# V01.net
KiCad netlist of a schematic drawn in EAGLE
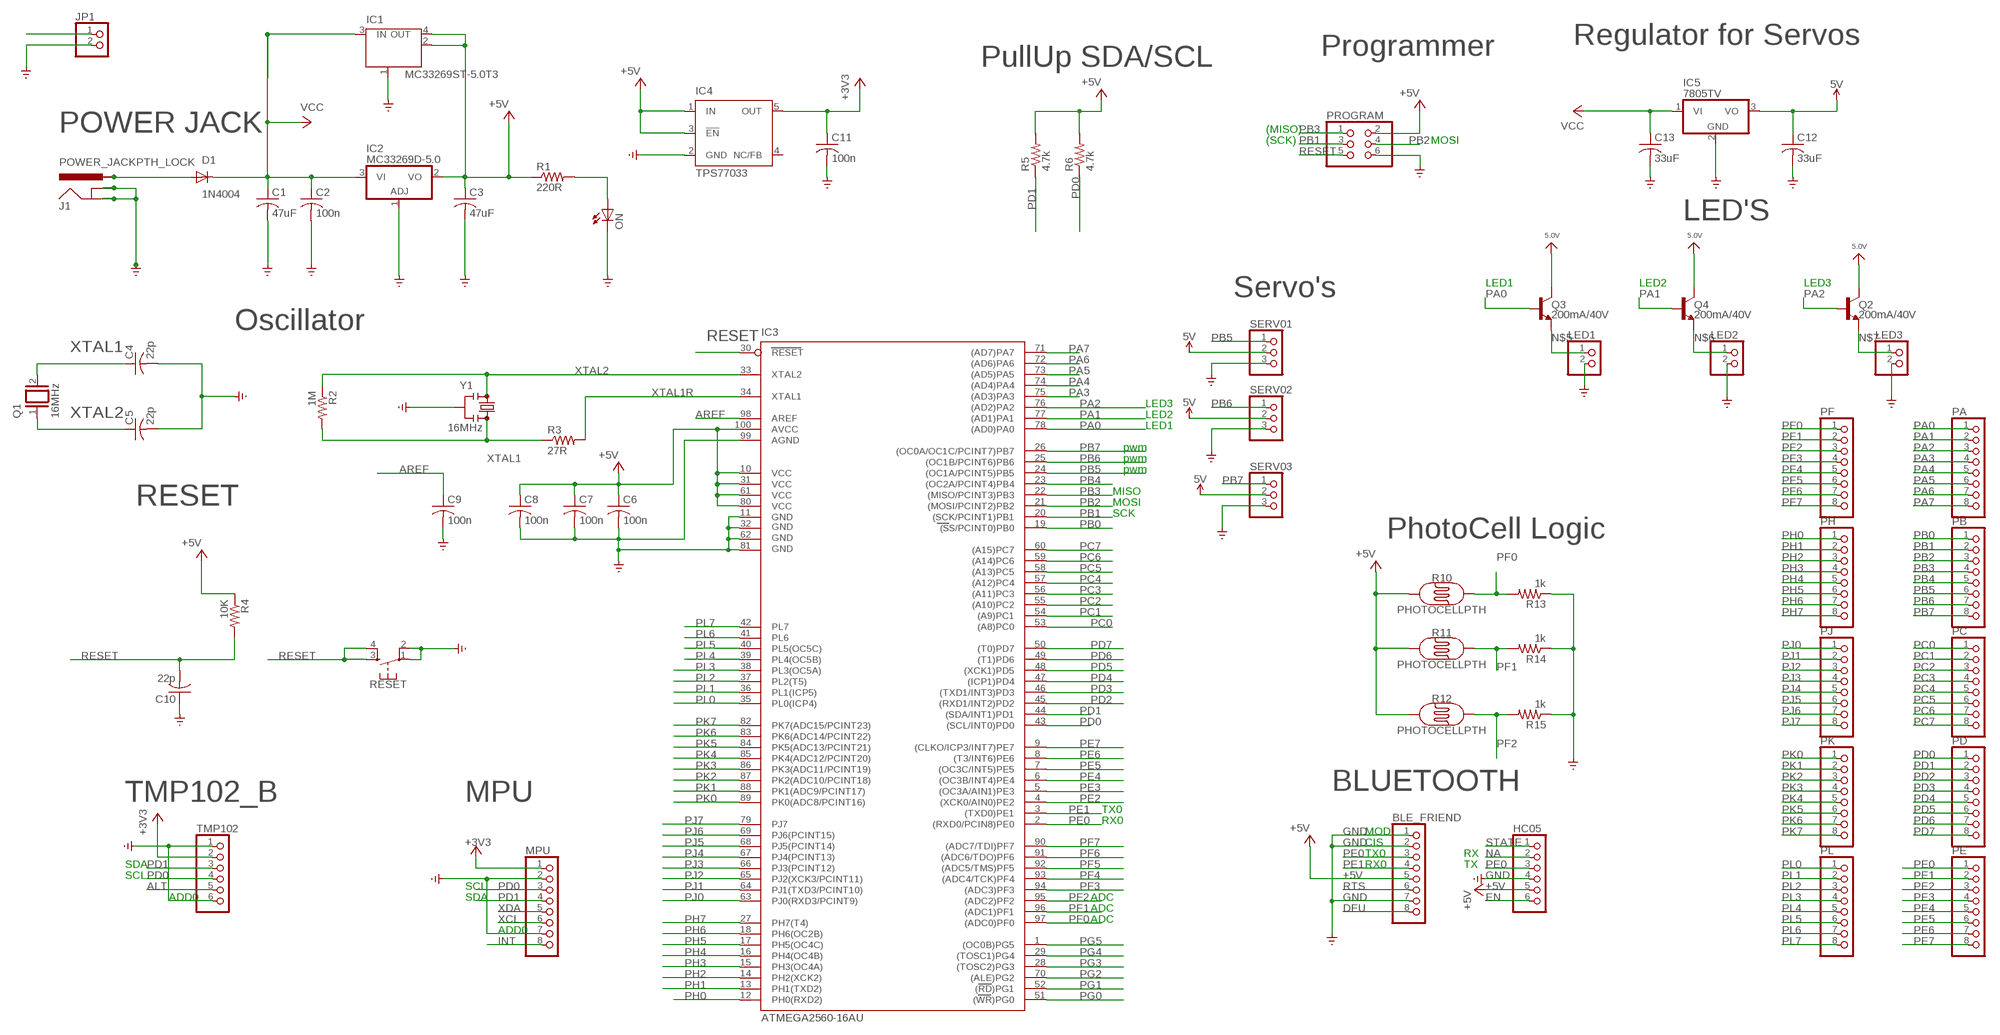
[diagram p0: schematic, sheet 1, part 1 of 2]
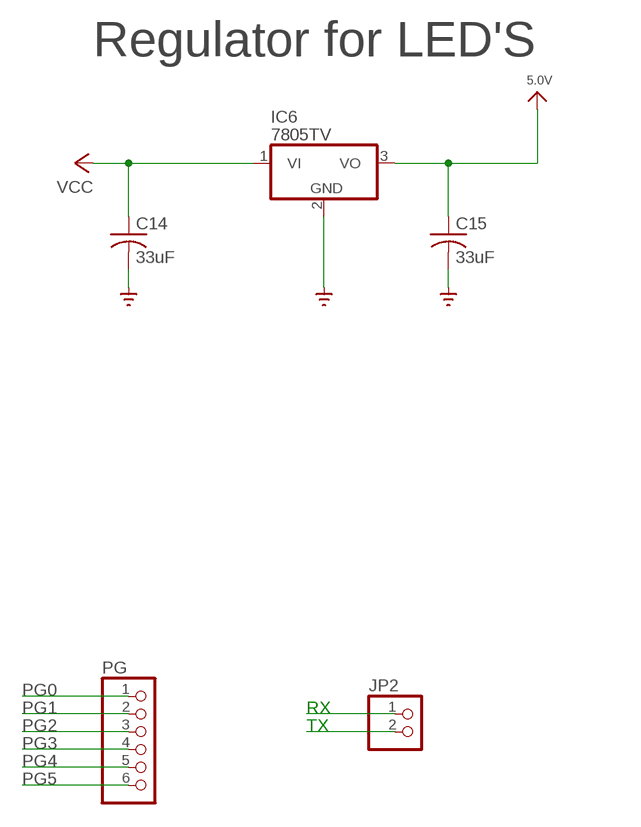
[diagram p1: schematic, sheet 1, part 2 of 2]

(export (version "E")
  (design (tool "Eeschema 10.0.6"))
  (components
    (comp (ref "BLE_FRIEND")
      (value "PINHD-1X8")
      (footprint "eagle-import:1X08")
      (libsource (lib "eagle-import") (part "PINHD-1X8"))
    )
    (comp (ref "C1")
      (value "47uF")
      (footprint "eagle-import:C025-024X044")
      (libsource (lib "eagle-import") (part "C-US025-024X044"))
    )
    (comp (ref "C2")
      (value "100n")
      (footprint "eagle-import:C025-024X044")
      (libsource (lib "eagle-import") (part "C-US025-024X044"))
    )
    (comp (ref "C3")
      (value "47uF")
      (footprint "eagle-import:C025-024X044")
      (libsource (lib "eagle-import") (part "C-US025-024X044"))
    )
    (comp (ref "C4")
      (value "22p")
      (footprint "eagle-import:C025-024X044")
      (libsource (lib "eagle-import") (part "C-US025-024X044"))
    )
    (comp (ref "C5")
      (value "22p")
      (footprint "eagle-import:C025-024X044")
      (libsource (lib "eagle-import") (part "C-US025-024X044"))
    )
    (comp (ref "C6")
      (value "100n")
      (footprint "eagle-import:C025-024X044")
      (libsource (lib "eagle-import") (part "C-US025-024X044"))
    )
    (comp (ref "C7")
      (value "100n")
      (footprint "eagle-import:C025-024X044")
      (libsource (lib "eagle-import") (part "C-US025-024X044"))
    )
    (comp (ref "C8")
      (value "100n")
      (footprint "eagle-import:C025-024X044")
      (libsource (lib "eagle-import") (part "C-US025-024X044"))
    )
    (comp (ref "C9")
      (value "100n")
      (footprint "eagle-import:C025-024X044")
      (libsource (lib "eagle-import") (part "C-US025-024X044"))
    )
    (comp (ref "C10")
      (value "22p")
      (footprint "eagle-import:C025-024X044")
      (libsource (lib "eagle-import") (part "C-US025-024X044"))
    )
    (comp (ref "C11")
      (value "100n")
      (footprint "eagle-import:C025-024X044")
      (libsource (lib "eagle-import") (part "C-US025-024X044"))
    )
    (comp (ref "C12")
      (value "33uF")
      (footprint "eagle-import:C025-024X044")
      (libsource (lib "eagle-import") (part "C-US025-024X044"))
    )
    (comp (ref "C13")
      (value "33uF")
      (footprint "eagle-import:C025-024X044")
      (libsource (lib "eagle-import") (part "C-US025-024X044"))
    )
    (comp (ref "C14")
      (value "33uF")
      (footprint "eagle-import:C025-024X044")
      (libsource (lib "eagle-import") (part "C-US025-024X044"))
    )
    (comp (ref "C15")
      (value "33uF")
      (footprint "eagle-import:C025-024X044")
      (libsource (lib "eagle-import") (part "C-US025-024X044"))
    )
    (comp (ref "D1")
      (value "1N4004")
      (footprint "eagle-import:DO41-10")
      (libsource (lib "eagle-import") (part "1N4004"))
    )
    (comp (ref "HC05")
      (value "PINHD-1X6")
      (footprint "eagle-import:1X06")
      (libsource (lib "eagle-import") (part "pinhead_325_PINHD-1X6"))
    )
    (comp (ref "IC1")
      (value "MC33269ST-5.0T3")
      (footprint "eagle-import:SOT223")
      (libsource (lib "eagle-import") (part "MC33269ST-3.3T3"))
    )
    (comp (ref "IC2")
      (value "MC33269D-5.0")
      (footprint "eagle-import:DPACK")
      (libsource (lib "eagle-import") (part "MC33269?D-5.0"))
    )
    (comp (ref "IC3")
      (value "ATMEGA2560-16AU")
      (footprint "eagle-import:TQFP100")
      (libsource (lib "eagle-import") (part "ATMEGAAU2560-16"))
    )
    (comp (ref "IC4")
      (value "TPS77033")
      (footprint "eagle-import:SOT23-DBV")
      (fields (field (name "MF") "TEXAS INSTRUMENTS") (field (name "MPN") "TPS77033DBVT"))
      (libsource (lib "eagle-import") (part "TPS77033"))
    )
    (comp (ref "IC5")
      (value "7805TV")
      (footprint "eagle-import:TO220V")
      (libsource (lib "eagle-import") (part "78TV05"))
    )
    (comp (ref "IC6")
      (value "7805TV")
      (footprint "eagle-import:TO220V")
      (libsource (lib "eagle-import") (part "78TV05"))
    )
    (comp (ref "J1")
      (value "POWER_JACKPTH_LOCK")
      (footprint "eagle-import:POWER_JACK_PTH_LOCK")
      (libsource (lib "eagle-import") (part "POWER_JACKPTH_LOCK"))
    )
    (comp (ref "JP1")
      (value "PINHD-1X2")
      (footprint "eagle-import:1X02")
      (libsource (lib "eagle-import") (part "PINHD-1X2"))
    )
    (comp (ref "JP2")
      (value "PINHD-1X2")
      (footprint "eagle-import:1X02")
      (libsource (lib "eagle-import") (part "pinhead_325_PINHD-1X2"))
    )
    (comp (ref "LED1")
      (value "PINHD-1X2")
      (footprint "eagle-import:1X02")
      (libsource (lib "eagle-import") (part "PINHD-1X2"))
    )
    (comp (ref "LED2")
      (value "PINHD-1X2")
      (footprint "eagle-import:1X02")
      (libsource (lib "eagle-import") (part "PINHD-1X2"))
    )
    (comp (ref "LED3")
      (value "PINHD-1X2")
      (footprint "eagle-import:1X02")
      (libsource (lib "eagle-import") (part "PINHD-1X2"))
    )
    (comp (ref "MPU")
      (value "PINHD-1X8")
      (footprint "eagle-import:1X08")
      (libsource (lib "eagle-import") (part "PINHD-1X8"))
    )
    (comp (ref "ON")
      (value "LED3MM")
      (footprint "eagle-import:LED3MM")
      (libsource (lib "eagle-import") (part "LED3MM"))
    )
    (comp (ref "PA")
      (value "PINHD-1X8")
      (footprint "eagle-import:1X08")
      (libsource (lib "eagle-import") (part "PINHD-1X8"))
    )
    (comp (ref "PB")
      (value "PINHD-1X8")
      (footprint "eagle-import:1X08")
      (libsource (lib "eagle-import") (part "PINHD-1X8"))
    )
    (comp (ref "PC")
      (value "PINHD-1X8")
      (footprint "eagle-import:1X08")
      (libsource (lib "eagle-import") (part "PINHD-1X8"))
    )
    (comp (ref "PD")
      (value "PINHD-1X8")
      (footprint "eagle-import:1X08")
      (libsource (lib "eagle-import") (part "PINHD-1X8"))
    )
    (comp (ref "PE")
      (value "PINHD-1X8")
      (footprint "eagle-import:1X08")
      (libsource (lib "eagle-import") (part "PINHD-1X8"))
    )
    (comp (ref "PF")
      (value "PINHD-1X8")
      (footprint "eagle-import:1X08")
      (libsource (lib "eagle-import") (part "PINHD-1X8"))
    )
    (comp (ref "PG")
      (value "PINHD-1X6")
      (footprint "eagle-import:1X06")
      (libsource (lib "eagle-import") (part "PINHD-1X6"))
    )
    (comp (ref "PH")
      (value "PINHD-1X8")
      (footprint "eagle-import:1X08")
      (libsource (lib "eagle-import") (part "PINHD-1X8"))
    )
    (comp (ref "PJ")
      (value "PINHD-1X8")
      (footprint "eagle-import:1X08")
      (libsource (lib "eagle-import") (part "PINHD-1X8"))
    )
    (comp (ref "PK")
      (value "PINHD-1X8")
      (footprint "eagle-import:1X08")
      (libsource (lib "eagle-import") (part "PINHD-1X8"))
    )
    (comp (ref "PL")
      (value "PINHD-1X8")
      (footprint "eagle-import:1X08")
      (libsource (lib "eagle-import") (part "PINHD-1X8"))
    )
    (comp (ref "PROGRAM")
      (value "PINHD-2X3")
      (footprint "eagle-import:2X03")
      (libsource (lib "eagle-import") (part "PINHD-2X3"))
    )
    (comp (ref "Q1")
      (value "16MHz")
      (footprint "eagle-import:QS")
      (libsource (lib "eagle-import") (part "XTAL/S"))
    )
    (comp (ref "Q2")
      (value "200mA/40V")
      (footprint "eagle-import:TO-92")
      (libsource (lib "eagle-import") (part "TRANS_NPN-2N3904"))
    )
    (comp (ref "Q3")
      (value "200mA/40V")
      (footprint "eagle-import:TO-92")
      (libsource (lib "eagle-import") (part "TRANS_NPN-2N3904"))
    )
    (comp (ref "Q4")
      (value "200mA/40V")
      (footprint "eagle-import:TO-92")
      (libsource (lib "eagle-import") (part "TRANS_NPN-2N3904"))
    )
    (comp (ref "R1")
      (value "220R")
      (footprint "eagle-import:0204V")
      (libsource (lib "eagle-import") (part "R-US_0204/2V"))
    )
    (comp (ref "R2")
      (value "1M")
      (footprint "eagle-import:0204V")
      (libsource (lib "eagle-import") (part "R-US_0204/2V"))
    )
    (comp (ref "R3")
      (value "27R")
      (footprint "eagle-import:0204V")
      (libsource (lib "eagle-import") (part "R-US_0204/2V"))
    )
    (comp (ref "R4")
      (value "10K")
      (footprint "eagle-import:0204V")
      (libsource (lib "eagle-import") (part "R-US_0204/2V"))
    )
    (comp (ref "R5")
      (value "4.7k")
      (footprint "eagle-import:0204V")
      (libsource (lib "eagle-import") (part "R-US_0204/2V"))
    )
    (comp (ref "R6")
      (value "4.7k")
      (footprint "eagle-import:0204V")
      (libsource (lib "eagle-import") (part "R-US_0204/2V"))
    )
    (comp (ref "R10")
      (value "PHOTOCELLPTH")
      (footprint "eagle-import:PHOTOCELL")
      (libsource (lib "eagle-import") (part "PHOTOCELLPTH"))
    )
    (comp (ref "R11")
      (value "PHOTOCELLPTH")
      (footprint "eagle-import:PHOTOCELL")
      (libsource (lib "eagle-import") (part "PHOTOCELLPTH"))
    )
    (comp (ref "R12")
      (value "PHOTOCELLPTH")
      (footprint "eagle-import:PHOTOCELL")
      (libsource (lib "eagle-import") (part "PHOTOCELLPTH"))
    )
    (comp (ref "R13")
      (value "1k")
      (footprint "eagle-import:0204V")
      (libsource (lib "eagle-import") (part "R-US_0204/2V"))
    )
    (comp (ref "R14")
      (value "1k")
      (footprint "eagle-import:0204V")
      (libsource (lib "eagle-import") (part "R-US_0204/2V"))
    )
    (comp (ref "R15")
      (value "1k")
      (footprint "eagle-import:0204V")
      (libsource (lib "eagle-import") (part "R-US_0204/2V"))
    )
    (comp (ref "RESET")
      (value "MOMENTARY-SWITCH-SPST-2-SMD-5.2MM")
      (footprint "eagle-import:TACTILE_SWITCH_SMD_5.2MM")
      (libsource (lib "eagle-import") (part "MOMENTARY-SWITCH-SPST-2-SMD-5.2MM"))
    )
    (comp (ref "SERV01")
      (value "PINHD-1X3")
      (footprint "eagle-import:1X03")
      (libsource (lib "eagle-import") (part "PINHD-1X3"))
    )
    (comp (ref "SERV02")
      (value "PINHD-1X3")
      (footprint "eagle-import:1X03")
      (libsource (lib "eagle-import") (part "PINHD-1X3"))
    )
    (comp (ref "SERV03")
      (value "PINHD-1X3")
      (footprint "eagle-import:1X03")
      (libsource (lib "eagle-import") (part "PINHD-1X3"))
    )
    (comp (ref "TMP102")
      (value "PINHD-1X6")
      (footprint "eagle-import:1X06")
      (libsource (lib "eagle-import") (part "PINHD-1X6"))
    )
    (comp (ref "Y1")
      (value "16MHz")
      (footprint "eagle-import:RESONATOR-SMD-3.2X1.3")
      (libsource (lib "eagle-import") (part "RESONATORSMD-3.2X1.3"))
    )
  )
  (nets
    (net (code "1") (name "+3V3") (class "Default")
      (node (ref "C11") (pin "1") (pinfunction "1_1") (pintype "passive"))
      (node (ref "IC4") (pin "5") (pinfunction "OUT_5") (pintype "passive"))
      (node (ref "MPU") (pin "1") (pinfunction "1_1") (pintype "passive"))
      (node (ref "TMP102") (pin "2") (pinfunction "2_2") (pintype "passive"))
    )
    (net (code "2") (name "+5V") (class "Default")
      (node (ref "BLE_FRIEND") (pin "5") (pinfunction "5_5") (pintype "passive"))
      (node (ref "C3") (pin "1") (pinfunction "1_1") (pintype "passive"))
      (node (ref "C6") (pin "1") (pinfunction "1_1") (pintype "passive"))
      (node (ref "C7") (pin "1") (pinfunction "1_1") (pintype "passive"))
      (node (ref "C8") (pin "1") (pinfunction "1_1") (pintype "passive"))
      (node (ref "HC05") (pin "5") (pinfunction "5_5") (pintype "passive"))
      (node (ref "IC1") (pin "2") (pinfunction "OUT_2") (pintype "passive"))
      (node (ref "IC1") (pin "4") (pinfunction "OUT_4") (pintype "passive"))
      (node (ref "IC2") (pin "2") (pinfunction "VO_2") (pintype "passive"))
      (node (ref "IC3") (pin "10") (pinfunction "VCC_10") (pintype "power_in"))
      (node (ref "IC3") (pin "100") (pinfunction "AVCC_100") (pintype "power_in"))
      (node (ref "IC3") (pin "31") (pinfunction "VCC1_31") (pintype "power_in"))
      (node (ref "IC3") (pin "61") (pinfunction "VCC2_61") (pintype "power_in"))
      (node (ref "IC3") (pin "80") (pinfunction "VCC3_80") (pintype "power_in"))
      (node (ref "IC4") (pin "1") (pinfunction "IN_1") (pintype "input"))
      (node (ref "IC4") (pin "3") (pinfunction "~{EN}_3") (pintype "input"))
      (node (ref "PROGRAM") (pin "2") (pinfunction "2_2") (pintype "passive"))
      (node (ref "R1") (pin "1") (pinfunction "1_1") (pintype "passive"))
      (node (ref "R10") (pin "1") (pinfunction "P$1_1") (pintype "bidirectional"))
      (node (ref "R11") (pin "1") (pinfunction "P$1_1") (pintype "bidirectional"))
      (node (ref "R12") (pin "1") (pinfunction "P$1_1") (pintype "bidirectional"))
      (node (ref "R4") (pin "1") (pinfunction "1_1") (pintype "passive"))
      (node (ref "R5") (pin "2") (pinfunction "2_2") (pintype "passive"))
      (node (ref "R6") (pin "2") (pinfunction "2_2") (pintype "passive"))
    )
    (net (code "3") (name "/ALT") (class "Default")
      (node (ref "TMP102") (pin "5") (pinfunction "5_5") (pintype "passive"))
    )
    (net (code "4") (name "/AREF") (class "Default")
      (node (ref "C9") (pin "1") (pinfunction "1_1") (pintype "passive"))
      (node (ref "IC3") (pin "98") (pinfunction "AREF_98") (pintype "bidirectional"))
    )
    (net (code "5") (name "/DFU") (class "Default")
      (node (ref "BLE_FRIEND") (pin "8") (pinfunction "8_8") (pintype "passive"))
    )
    (net (code "6") (name "/EN") (class "Default")
      (node (ref "HC05") (pin "6") (pinfunction "6_6") (pintype "passive"))
    )
    (net (code "7") (name "/INT") (class "Default")
      (node (ref "MPU") (pin "8") (pinfunction "8_8") (pintype "passive"))
    )
    (net (code "8") (name "/N$5") (class "Default")
      (node (ref "LED1") (pin "1") (pinfunction "1_1") (pintype "passive"))
      (node (ref "Q3") (pin "1") (pinfunction "E_1") (pintype "passive"))
    )
    (net (code "9") (name "/N$6") (class "Default")
      (node (ref "LED2") (pin "1") (pinfunction "1_1") (pintype "passive"))
      (node (ref "Q4") (pin "1") (pinfunction "E_1") (pintype "passive"))
    )
    (net (code "10") (name "/N$7") (class "Default")
      (node (ref "LED3") (pin "1") (pinfunction "1_1") (pintype "passive"))
      (node (ref "Q2") (pin "1") (pinfunction "E_1") (pintype "passive"))
    )
    (net (code "11") (name "/NA") (class "Default")
      (node (ref "HC05") (pin "2") (pinfunction "2_2") (pintype "passive"))
    )
    (net (code "12") (name "/PA0") (class "Default")
      (node (ref "IC3") (pin "78") (pinfunction "(AD0)PA0_78") (pintype "bidirectional"))
      (node (ref "PA") (pin "1") (pinfunction "1_1") (pintype "passive"))
      (node (ref "Q3") (pin "2") (pinfunction "B_2") (pintype "passive"))
    )
    (net (code "13") (name "/PA1") (class "Default")
      (node (ref "IC3") (pin "77") (pinfunction "(AD1)PA1_77") (pintype "bidirectional"))
      (node (ref "PA") (pin "2") (pinfunction "2_2") (pintype "passive"))
      (node (ref "Q4") (pin "2") (pinfunction "B_2") (pintype "passive"))
    )
    (net (code "14") (name "/PA2") (class "Default")
      (node (ref "IC3") (pin "76") (pinfunction "(AD2)PA2_76") (pintype "bidirectional"))
      (node (ref "PA") (pin "3") (pinfunction "3_3") (pintype "passive"))
      (node (ref "Q2") (pin "2") (pinfunction "B_2") (pintype "passive"))
    )
    (net (code "15") (name "/PA3") (class "Default")
      (node (ref "IC3") (pin "75") (pinfunction "(AD3)PA3_75") (pintype "bidirectional"))
      (node (ref "PA") (pin "4") (pinfunction "4_4") (pintype "passive"))
    )
    (net (code "16") (name "/PA4") (class "Default")
      (node (ref "IC3") (pin "74") (pinfunction "(AD4)PA4_74") (pintype "bidirectional"))
      (node (ref "PA") (pin "5") (pinfunction "5_5") (pintype "passive"))
    )
    (net (code "17") (name "/PA5") (class "Default")
      (node (ref "IC3") (pin "73") (pinfunction "(AD5)PA5_73") (pintype "bidirectional"))
      (node (ref "PA") (pin "6") (pinfunction "6_6") (pintype "passive"))
    )
    (net (code "18") (name "/PA6") (class "Default")
      (node (ref "IC3") (pin "72") (pinfunction "(AD6)PA6_72") (pintype "bidirectional"))
      (node (ref "PA") (pin "7") (pinfunction "7_7") (pintype "passive"))
    )
    (net (code "19") (name "/PA7") (class "Default")
      (node (ref "IC3") (pin "71") (pinfunction "(AD7)PA7_71") (pintype "bidirectional"))
      (node (ref "PA") (pin "8") (pinfunction "8_8") (pintype "passive"))
    )
    (net (code "20") (name "/PB0") (class "Default")
      (node (ref "IC3") (pin "19") (pinfunction "(SS/PCINT0)PB0_19") (pintype "bidirectional"))
      (node (ref "PB") (pin "1") (pinfunction "1_1") (pintype "passive"))
    )
    (net (code "21") (name "/PB1") (class "Default")
      (node (ref "IC3") (pin "20") (pinfunction "(SCK/PCINT1)PB1_20") (pintype "bidirectional"))
      (node (ref "PB") (pin "2") (pinfunction "2_2") (pintype "passive"))
      (node (ref "PROGRAM") (pin "3") (pinfunction "3_3") (pintype "passive"))
    )
    (net (code "22") (name "/PB2") (class "Default")
      (node (ref "IC3") (pin "21") (pinfunction "(MOSI/PCINT2)PB2_21") (pintype "bidirectional"))
      (node (ref "PB") (pin "3") (pinfunction "3_3") (pintype "passive"))
      (node (ref "PROGRAM") (pin "4") (pinfunction "4_4") (pintype "passive"))
    )
    (net (code "23") (name "/PB3") (class "Default")
      (node (ref "IC3") (pin "22") (pinfunction "(MISO/PCINT3)PB3_22") (pintype "bidirectional"))
      (node (ref "PB") (pin "4") (pinfunction "4_4") (pintype "passive"))
      (node (ref "PROGRAM") (pin "1") (pinfunction "1_1") (pintype "passive"))
    )
    (net (code "24") (name "/PB4") (class "Default")
      (node (ref "IC3") (pin "23") (pinfunction "(OC2A/PCINT4)PB4_23") (pintype "bidirectional"))
      (node (ref "PB") (pin "5") (pinfunction "5_5") (pintype "passive"))
    )
    (net (code "25") (name "/PB5") (class "Default")
      (node (ref "IC3") (pin "24") (pinfunction "(OC1A/PCINT5)PB5_24") (pintype "bidirectional"))
      (node (ref "PB") (pin "6") (pinfunction "6_6") (pintype "passive"))
      (node (ref "SERV01") (pin "1") (pinfunction "1_1") (pintype "passive"))
    )
    (net (code "26") (name "/PB6") (class "Default")
      (node (ref "IC3") (pin "25") (pinfunction "(OC1B/PCINT6)PB6_25") (pintype "bidirectional"))
      (node (ref "PB") (pin "7") (pinfunction "7_7") (pintype "passive"))
      (node (ref "SERV02") (pin "1") (pinfunction "1_1") (pintype "passive"))
    )
    (net (code "27") (name "/PB7") (class "Default")
      (node (ref "IC3") (pin "26") (pinfunction "(OC0A/OC1C/PCINT7)PB7_26") (pintype "bidirectional"))
      (node (ref "PB") (pin "8") (pinfunction "8_8") (pintype "passive"))
      (node (ref "SERV03") (pin "1") (pinfunction "1_1") (pintype "passive"))
    )
    (net (code "28") (name "/PC0") (class "Default")
      (node (ref "IC3") (pin "53") (pinfunction "(A8)PC0_53") (pintype "bidirectional"))
      (node (ref "PC") (pin "1") (pinfunction "1_1") (pintype "passive"))
    )
    (net (code "29") (name "/PC1") (class "Default")
      (node (ref "IC3") (pin "54") (pinfunction "(A9)PC1_54") (pintype "bidirectional"))
      (node (ref "PC") (pin "2") (pinfunction "2_2") (pintype "passive"))
    )
    (net (code "30") (name "/PC2") (class "Default")
      (node (ref "IC3") (pin "55") (pinfunction "(A10)PC2_55") (pintype "bidirectional"))
      (node (ref "PC") (pin "3") (pinfunction "3_3") (pintype "passive"))
    )
    (net (code "31") (name "/PC3") (class "Default")
      (node (ref "IC3") (pin "56") (pinfunction "(A11)PC3_56") (pintype "bidirectional"))
      (node (ref "PC") (pin "4") (pinfunction "4_4") (pintype "passive"))
    )
    (net (code "32") (name "/PC4") (class "Default")
      (node (ref "IC3") (pin "57") (pinfunction "(A12)PC4_57") (pintype "bidirectional"))
      (node (ref "PC") (pin "5") (pinfunction "5_5") (pintype "passive"))
    )
    (net (code "33") (name "/PC5") (class "Default")
      (node (ref "IC3") (pin "58") (pinfunction "(A13)PC5_58") (pintype "bidirectional"))
      (node (ref "PC") (pin "6") (pinfunction "6_6") (pintype "passive"))
    )
    (net (code "34") (name "/PC6") (class "Default")
      (node (ref "IC3") (pin "59") (pinfunction "(A14)PC6_59") (pintype "bidirectional"))
      (node (ref "PC") (pin "7") (pinfunction "7_7") (pintype "passive"))
    )
    (net (code "35") (name "/PC7") (class "Default")
      (node (ref "IC3") (pin "60") (pinfunction "(A15)PC7_60") (pintype "bidirectional"))
      (node (ref "PC") (pin "8") (pinfunction "8_8") (pintype "passive"))
    )
    (net (code "36") (name "/PD0") (class "Default")
      (node (ref "IC3") (pin "43") (pinfunction "(SCL/INT0)PD0_43") (pintype "bidirectional"))
      (node (ref "MPU") (pin "3") (pinfunction "3_3") (pintype "passive"))
      (node (ref "PD") (pin "1") (pinfunction "1_1") (pintype "passive"))
      (node (ref "R6") (pin "1") (pinfunction "1_1") (pintype "passive"))
      (node (ref "TMP102") (pin "4") (pinfunction "4_4") (pintype "passive"))
    )
    (net (code "37") (name "/PD1") (class "Default")
      (node (ref "IC3") (pin "44") (pinfunction "(SDA/INT1)PD1_44") (pintype "bidirectional"))
      (node (ref "MPU") (pin "4") (pinfunction "4_4") (pintype "passive"))
      (node (ref "PD") (pin "2") (pinfunction "2_2") (pintype "passive"))
      (node (ref "R5") (pin "1") (pinfunction "1_1") (pintype "passive"))
      (node (ref "TMP102") (pin "3") (pinfunction "3_3") (pintype "passive"))
    )
    (net (code "38") (name "/PD2") (class "Default")
      (node (ref "IC3") (pin "45") (pinfunction "(RXD1/INT2)PD2_45") (pintype "bidirectional"))
      (node (ref "PD") (pin "3") (pinfunction "3_3") (pintype "passive"))
    )
    (net (code "39") (name "/PD3") (class "Default")
      (node (ref "IC3") (pin "46") (pinfunction "(TXD1/INT3)PD3_46") (pintype "bidirectional"))
      (node (ref "PD") (pin "4") (pinfunction "4_4") (pintype "passive"))
    )
    (net (code "40") (name "/PD4") (class "Default")
      (node (ref "IC3") (pin "47") (pinfunction "(ICP1)PD4_47") (pintype "bidirectional"))
      (node (ref "PD") (pin "5") (pinfunction "5_5") (pintype "passive"))
    )
    (net (code "41") (name "/PD5") (class "Default")
      (node (ref "IC3") (pin "48") (pinfunction "(XCK1)PD5_48") (pintype "bidirectional"))
      (node (ref "PD") (pin "6") (pinfunction "6_6") (pintype "passive"))
    )
    (net (code "42") (name "/PD6") (class "Default")
      (node (ref "IC3") (pin "49") (pinfunction "(T1)PD6_49") (pintype "bidirectional"))
      (node (ref "PD") (pin "7") (pinfunction "7_7") (pintype "passive"))
    )
    (net (code "43") (name "/PD7") (class "Default")
      (node (ref "IC3") (pin "50") (pinfunction "(T0)PD7_50") (pintype "bidirectional"))
      (node (ref "PD") (pin "8") (pinfunction "8_8") (pintype "passive"))
    )
    (net (code "44") (name "/PE0") (class "Default")
      (node (ref "BLE_FRIEND") (pin "3") (pinfunction "3_3") (pintype "passive"))
      (node (ref "HC05") (pin "3") (pinfunction "3_3") (pintype "passive"))
      (node (ref "IC3") (pin "2") (pinfunction "(RXD0/PCIN8)PE0_2") (pintype "bidirectional"))
      (node (ref "JP2") (pin "1") (pinfunction "1_1") (pintype "passive"))
      (node (ref "PE") (pin "1") (pinfunction "1_1") (pintype "passive"))
    )
    (net (code "45") (name "/PE1") (class "Default")
      (node (ref "BLE_FRIEND") (pin "4") (pinfunction "4_4") (pintype "passive"))
      (node (ref "IC3") (pin "3") (pinfunction "(TXD0)PE1_3") (pintype "bidirectional"))
      (node (ref "JP2") (pin "2") (pinfunction "2_2") (pintype "passive"))
      (node (ref "PE") (pin "2") (pinfunction "2_2") (pintype "passive"))
    )
    (net (code "46") (name "/PE2") (class "Default")
      (node (ref "IC3") (pin "4") (pinfunction "(XCK0/AIN0)PE2_4") (pintype "bidirectional"))
      (node (ref "PE") (pin "3") (pinfunction "3_3") (pintype "passive"))
    )
    (net (code "47") (name "/PE3") (class "Default")
      (node (ref "IC3") (pin "5") (pinfunction "(OC3A/AIN1)PE3_5") (pintype "bidirectional"))
      (node (ref "PE") (pin "4") (pinfunction "4_4") (pintype "passive"))
    )
    (net (code "48") (name "/PE4") (class "Default")
      (node (ref "IC3") (pin "6") (pinfunction "(OC3B/INT4)PE4_6") (pintype "bidirectional"))
      (node (ref "PE") (pin "5") (pinfunction "5_5") (pintype "passive"))
    )
    (net (code "49") (name "/PE5") (class "Default")
      (node (ref "IC3") (pin "7") (pinfunction "(OC3C/INT5)PE5_7") (pintype "bidirectional"))
      (node (ref "PE") (pin "6") (pinfunction "6_6") (pintype "passive"))
    )
    (net (code "50") (name "/PE6") (class "Default")
      (node (ref "IC3") (pin "8") (pinfunction "(T3/INT6)PE6_8") (pintype "bidirectional"))
      (node (ref "PE") (pin "7") (pinfunction "7_7") (pintype "passive"))
    )
    (net (code "51") (name "/PE7") (class "Default")
      (node (ref "IC3") (pin "9") (pinfunction "(CLKO/ICP3/INT7)PE7_9") (pintype "bidirectional"))
      (node (ref "PE") (pin "8") (pinfunction "8_8") (pintype "passive"))
    )
    (net (code "52") (name "/PF0") (class "Default")
      (node (ref "IC3") (pin "97") (pinfunction "(ADC0)PF0_97") (pintype "bidirectional"))
      (node (ref "PF") (pin "1") (pinfunction "1_1") (pintype "passive"))
      (node (ref "R10") (pin "2") (pinfunction "P$2_2") (pintype "bidirectional"))
      (node (ref "R13") (pin "2") (pinfunction "2_2") (pintype "passive"))
    )
    (net (code "53") (name "/PF1") (class "Default")
      (node (ref "IC3") (pin "96") (pinfunction "(ADC1)PF1_96") (pintype "bidirectional"))
      (node (ref "PF") (pin "2") (pinfunction "2_2") (pintype "passive"))
      (node (ref "R11") (pin "2") (pinfunction "P$2_2") (pintype "bidirectional"))
      (node (ref "R14") (pin "2") (pinfunction "2_2") (pintype "passive"))
    )
    (net (code "54") (name "/PF2") (class "Default")
      (node (ref "IC3") (pin "95") (pinfunction "(ADC2)PF2_95") (pintype "bidirectional"))
      (node (ref "PF") (pin "3") (pinfunction "3_3") (pintype "passive"))
      (node (ref "R12") (pin "2") (pinfunction "P$2_2") (pintype "bidirectional"))
      (node (ref "R15") (pin "2") (pinfunction "2_2") (pintype "passive"))
    )
    (net (code "55") (name "/PF3") (class "Default")
      (node (ref "IC3") (pin "94") (pinfunction "(ADC3)PF3_94") (pintype "bidirectional"))
      (node (ref "PF") (pin "4") (pinfunction "4_4") (pintype "passive"))
    )
    (net (code "56") (name "/PF4") (class "Default")
      (node (ref "IC3") (pin "93") (pinfunction "(ADC4/TCK)PF4_93") (pintype "bidirectional"))
      (node (ref "PF") (pin "5") (pinfunction "5_5") (pintype "passive"))
    )
    (net (code "57") (name "/PF5") (class "Default")
      (node (ref "IC3") (pin "92") (pinfunction "(ADC5/TMS)PF5_92") (pintype "bidirectional"))
      (node (ref "PF") (pin "6") (pinfunction "6_6") (pintype "passive"))
    )
    (net (code "58") (name "/PF6") (class "Default")
      (node (ref "IC3") (pin "91") (pinfunction "(ADC6/TDO)PF6_91") (pintype "bidirectional"))
      (node (ref "PF") (pin "7") (pinfunction "7_7") (pintype "passive"))
    )
    (net (code "59") (name "/PF7") (class "Default")
      (node (ref "IC3") (pin "90") (pinfunction "(ADC7/TDI)PF7_90") (pintype "bidirectional"))
      (node (ref "PF") (pin "8") (pinfunction "8_8") (pintype "passive"))
    )
    (net (code "60") (name "/PG0") (class "Default")
      (node (ref "IC3") (pin "51") (pinfunction "(WR)PG0_51") (pintype "bidirectional"))
      (node (ref "PG") (pin "1") (pinfunction "1_1") (pintype "passive"))
    )
    (net (code "61") (name "/PG1") (class "Default")
      (node (ref "IC3") (pin "52") (pinfunction "(RD)PG1_52") (pintype "bidirectional"))
      (node (ref "PG") (pin "2") (pinfunction "2_2") (pintype "passive"))
    )
    (net (code "62") (name "/PG2") (class "Default")
      (node (ref "IC3") (pin "70") (pinfunction "(ALE)PG2_70") (pintype "bidirectional"))
      (node (ref "PG") (pin "3") (pinfunction "3_3") (pintype "passive"))
    )
    (net (code "63") (name "/PG3") (class "Default")
      (node (ref "IC3") (pin "28") (pinfunction "(TOSC2)PG3_28") (pintype "bidirectional"))
      (node (ref "PG") (pin "4") (pinfunction "4_4") (pintype "passive"))
    )
    (net (code "64") (name "/PG4") (class "Default")
      (node (ref "IC3") (pin "29") (pinfunction "(TOSC1)PG4_29") (pintype "bidirectional"))
      (node (ref "PG") (pin "5") (pinfunction "5_5") (pintype "passive"))
    )
    (net (code "65") (name "/PG5") (class "Default")
      (node (ref "IC3") (pin "1") (pinfunction "(OC0B)PG5_1") (pintype "bidirectional"))
      (node (ref "PG") (pin "6") (pinfunction "6_6") (pintype "passive"))
    )
    (net (code "66") (name "/PH0") (class "Default")
      (node (ref "IC3") (pin "12") (pinfunction "PH0(RXD2)_12") (pintype "bidirectional"))
      (node (ref "PH") (pin "1") (pinfunction "1_1") (pintype "passive"))
    )
    (net (code "67") (name "/PH1") (class "Default")
      (node (ref "IC3") (pin "13") (pinfunction "PH1(TXD2)_13") (pintype "bidirectional"))
      (node (ref "PH") (pin "2") (pinfunction "2_2") (pintype "passive"))
    )
    (net (code "68") (name "/PH2") (class "Default")
      (node (ref "IC3") (pin "14") (pinfunction "PH2(XCK2)_14") (pintype "bidirectional"))
      (node (ref "PH") (pin "3") (pinfunction "3_3") (pintype "passive"))
    )
    (net (code "69") (name "/PH3") (class "Default")
      (node (ref "IC3") (pin "15") (pinfunction "PH3(OC4A)_15") (pintype "bidirectional"))
      (node (ref "PH") (pin "4") (pinfunction "4_4") (pintype "passive"))
    )
    (net (code "70") (name "/PH4") (class "Default")
      (node (ref "IC3") (pin "16") (pinfunction "PH4(OC4B)_16") (pintype "bidirectional"))
      (node (ref "PH") (pin "5") (pinfunction "5_5") (pintype "passive"))
    )
    (net (code "71") (name "/PH5") (class "Default")
      (node (ref "IC3") (pin "17") (pinfunction "PH5(OC4C)_17") (pintype "bidirectional"))
      (node (ref "PH") (pin "6") (pinfunction "6_6") (pintype "passive"))
    )
    (net (code "72") (name "/PH6") (class "Default")
      (node (ref "IC3") (pin "18") (pinfunction "PH6(OC2B)_18") (pintype "bidirectional"))
      (node (ref "PH") (pin "7") (pinfunction "7_7") (pintype "passive"))
    )
    (net (code "73") (name "/PH7") (class "Default")
      (node (ref "IC3") (pin "27") (pinfunction "PH7(T4)_27") (pintype "bidirectional"))
      (node (ref "PH") (pin "8") (pinfunction "8_8") (pintype "passive"))
    )
    (net (code "74") (name "/PJ0") (class "Default")
      (node (ref "IC3") (pin "63") (pinfunction "PJ0(RXD3/PCINT9)_63") (pintype "bidirectional"))
      (node (ref "PJ") (pin "1") (pinfunction "1_1") (pintype "passive"))
    )
    (net (code "75") (name "/PJ1") (class "Default")
      (node (ref "IC3") (pin "64") (pinfunction "PJ1(TXD3/PCINT10)_64") (pintype "bidirectional"))
      (node (ref "PJ") (pin "2") (pinfunction "2_2") (pintype "passive"))
    )
    (net (code "76") (name "/PJ2") (class "Default")
      (node (ref "IC3") (pin "65") (pinfunction "PJ2(XCK3/PCINT11)_65") (pintype "bidirectional"))
      (node (ref "PJ") (pin "3") (pinfunction "3_3") (pintype "passive"))
    )
    (net (code "77") (name "/PJ3") (class "Default")
      (node (ref "IC3") (pin "66") (pinfunction "PJ3(PCINT12)_66") (pintype "bidirectional"))
      (node (ref "PJ") (pin "4") (pinfunction "4_4") (pintype "passive"))
    )
    (net (code "78") (name "/PJ4") (class "Default")
      (node (ref "IC3") (pin "67") (pinfunction "PJ4(PCINT13)_67") (pintype "bidirectional"))
      (node (ref "PJ") (pin "5") (pinfunction "5_5") (pintype "passive"))
    )
    (net (code "79") (name "/PJ5") (class "Default")
      (node (ref "IC3") (pin "68") (pinfunction "PJ5(PCINT14)_68") (pintype "bidirectional"))
      (node (ref "PJ") (pin "6") (pinfunction "6_6") (pintype "passive"))
    )
    (net (code "80") (name "/PJ6") (class "Default")
      (node (ref "IC3") (pin "69") (pinfunction "PJ6(PCINT15)_69") (pintype "bidirectional"))
      (node (ref "PJ") (pin "7") (pinfunction "7_7") (pintype "passive"))
    )
    (net (code "81") (name "/PJ7") (class "Default")
      (node (ref "IC3") (pin "79") (pinfunction "PJ7_79") (pintype "bidirectional"))
      (node (ref "PJ") (pin "8") (pinfunction "8_8") (pintype "passive"))
    )
    (net (code "82") (name "/PK0") (class "Default")
      (node (ref "IC3") (pin "89") (pinfunction "PK0(ADC8/PCINT16)_89") (pintype "bidirectional"))
      (node (ref "PK") (pin "1") (pinfunction "1_1") (pintype "passive"))
    )
    (net (code "83") (name "/PK1") (class "Default")
      (node (ref "IC3") (pin "88") (pinfunction "PK1(ADC9/PCINT17)_88") (pintype "bidirectional"))
      (node (ref "PK") (pin "2") (pinfunction "2_2") (pintype "passive"))
    )
    (net (code "84") (name "/PK2") (class "Default")
      (node (ref "IC3") (pin "87") (pinfunction "PK2(ADC10/PCINT18)_87") (pintype "bidirectional"))
      (node (ref "PK") (pin "3") (pinfunction "3_3") (pintype "passive"))
    )
    (net (code "85") (name "/PK3") (class "Default")
      (node (ref "IC3") (pin "86") (pinfunction "PK3(ADC11/PCINT19)_86") (pintype "bidirectional"))
      (node (ref "PK") (pin "4") (pinfunction "4_4") (pintype "passive"))
    )
    (net (code "86") (name "/PK4") (class "Default")
      (node (ref "IC3") (pin "85") (pinfunction "PK4(ADC12/PCINT20)_85") (pintype "bidirectional"))
      (node (ref "PK") (pin "5") (pinfunction "5_5") (pintype "passive"))
    )
    (net (code "87") (name "/PK5") (class "Default")
      (node (ref "IC3") (pin "84") (pinfunction "PK5(ADC13/PCINT21)_84") (pintype "bidirectional"))
      (node (ref "PK") (pin "6") (pinfunction "6_6") (pintype "passive"))
    )
    (net (code "88") (name "/PK6") (class "Default")
      (node (ref "IC3") (pin "83") (pinfunction "PK6(ADC14/PCINT22)_83") (pintype "bidirectional"))
      (node (ref "PK") (pin "7") (pinfunction "7_7") (pintype "passive"))
    )
    (net (code "89") (name "/PK7") (class "Default")
      (node (ref "IC3") (pin "82") (pinfunction "PK7(ADC15/PCINT23)_82") (pintype "bidirectional"))
      (node (ref "PK") (pin "8") (pinfunction "8_8") (pintype "passive"))
    )
    (net (code "90") (name "/PL0") (class "Default")
      (node (ref "IC3") (pin "35") (pinfunction "PL0(ICP4)_35") (pintype "bidirectional"))
      (node (ref "PL") (pin "1") (pinfunction "1_1") (pintype "passive"))
    )
    (net (code "91") (name "/PL1") (class "Default")
      (node (ref "IC3") (pin "36") (pinfunction "PL1(ICP5)_36") (pintype "bidirectional"))
      (node (ref "PL") (pin "2") (pinfunction "2_2") (pintype "passive"))
    )
    (net (code "92") (name "/PL2") (class "Default")
      (node (ref "IC3") (pin "37") (pinfunction "PL2(T5)_37") (pintype "bidirectional"))
      (node (ref "PL") (pin "3") (pinfunction "3_3") (pintype "passive"))
    )
    (net (code "93") (name "/PL3") (class "Default")
      (node (ref "IC3") (pin "38") (pinfunction "PL3(OC5A)_38") (pintype "bidirectional"))
      (node (ref "PL") (pin "4") (pinfunction "4_4") (pintype "passive"))
    )
    (net (code "94") (name "/PL4") (class "Default")
      (node (ref "IC3") (pin "39") (pinfunction "PL4(OC5B)_39") (pintype "bidirectional"))
      (node (ref "PL") (pin "5") (pinfunction "5_5") (pintype "passive"))
    )
    (net (code "95") (name "/PL5") (class "Default")
      (node (ref "IC3") (pin "40") (pinfunction "PL5(OC5C)_40") (pintype "bidirectional"))
      (node (ref "PL") (pin "6") (pinfunction "6_6") (pintype "passive"))
    )
    (net (code "96") (name "/PL6") (class "Default")
      (node (ref "IC3") (pin "41") (pinfunction "PL6_41") (pintype "bidirectional"))
      (node (ref "PL") (pin "7") (pinfunction "7_7") (pintype "passive"))
    )
    (net (code "97") (name "/PL7") (class "Default")
      (node (ref "IC3") (pin "42") (pinfunction "PL7_42") (pintype "bidirectional"))
      (node (ref "PL") (pin "8") (pinfunction "8_8") (pintype "passive"))
    )
    (net (code "98") (name "/POWERIN") (class "Default")
      (node (ref "D1") (pin "A") (pinfunction "A_A") (pintype "passive"))
      (node (ref "J1") (pin "PWR") (pinfunction "PWR_PWR") (pintype "bidirectional"))
      (node (ref "JP1") (pin "1") (pinfunction "1_1") (pintype "passive"))
    )
    (net (code "99") (name "/RESET") (class "Default")
      (node (ref "C10") (pin "2") (pinfunction "2_2") (pintype "passive"))
      (node (ref "IC3") (pin "30") (pinfunction "RESET_30") (pintype "input"))
      (node (ref "PROGRAM") (pin "5") (pinfunction "5_5") (pintype "passive"))
      (node (ref "R4") (pin "2") (pinfunction "2_2") (pintype "passive"))
      (node (ref "RESET") (pin "3") (pinfunction "3_3") (pintype "passive"))
      (node (ref "RESET") (pin "4") (pinfunction "4_4") (pintype "passive"))
    )
    (net (code "100") (name "/RTS") (class "Default")
      (node (ref "BLE_FRIEND") (pin "6") (pinfunction "6_6") (pintype "passive"))
    )
    (net (code "101") (name "/STATE") (class "Default")
      (node (ref "HC05") (pin "1") (pinfunction "1_1") (pintype "passive"))
    )
    (net (code "102") (name "/XCL") (class "Default")
      (node (ref "MPU") (pin "6") (pinfunction "6_6") (pintype "passive"))
    )
    (net (code "103") (name "/XDA") (class "Default")
      (node (ref "MPU") (pin "5") (pinfunction "5_5") (pintype "passive"))
    )
    (net (code "104") (name "/XTAL1") (class "Default")
      (node (ref "C4") (pin "1") (pinfunction "1_1") (pintype "passive"))
      (node (ref "Q1") (pin "2") (pinfunction "2_2") (pintype "passive"))
      (node (ref "R2") (pin "2") (pinfunction "2_2") (pintype "passive"))
      (node (ref "R3") (pin "1") (pinfunction "1_1") (pintype "passive"))
      (node (ref "Y1") (pin "3") (pinfunction "3_3") (pintype "passive"))
    )
    (net (code "105") (name "/XTAL1R") (class "Default")
      (node (ref "IC3") (pin "34") (pinfunction "XTAL1_34") (pintype "input"))
      (node (ref "R3") (pin "2") (pinfunction "2_2") (pintype "passive"))
    )
    (net (code "106") (name "/XTAL2") (class "Default")
      (node (ref "C5") (pin "1") (pinfunction "1_1") (pintype "passive"))
      (node (ref "IC3") (pin "33") (pinfunction "XTAL2_33") (pintype "output"))
      (node (ref "Q1") (pin "1") (pinfunction "1_1") (pintype "passive"))
      (node (ref "R2") (pin "1") (pinfunction "1_1") (pintype "passive"))
      (node (ref "Y1") (pin "1") (pinfunction "1_1") (pintype "passive"))
    )
    (net (code "107") (name "5.0V") (class "Default")
      (node (ref "C15") (pin "1") (pinfunction "1_1") (pintype "passive"))
      (node (ref "IC6") (pin "3") (pinfunction "VO_3") (pintype "passive"))
      (node (ref "Q2") (pin "3") (pinfunction "C_3") (pintype "passive"))
      (node (ref "Q3") (pin "3") (pinfunction "C_3") (pintype "passive"))
      (node (ref "Q4") (pin "3") (pinfunction "C_3") (pintype "passive"))
    )
    (net (code "108") (name "5V") (class "Default")
      (node (ref "C12") (pin "1") (pinfunction "1_1") (pintype "passive"))
      (node (ref "IC5") (pin "3") (pinfunction "VO_3") (pintype "passive"))
      (node (ref "SERV01") (pin "2") (pinfunction "2_2") (pintype "passive"))
      (node (ref "SERV02") (pin "2") (pinfunction "2_2") (pintype "passive"))
      (node (ref "SERV03") (pin "2") (pinfunction "2_2") (pintype "passive"))
    )
    (net (code "109") (name "GND_") (class "Default")
      (node (ref "BLE_FRIEND") (pin "1") (pinfunction "1_1") (pintype "passive"))
      (node (ref "BLE_FRIEND") (pin "2") (pinfunction "2_2") (pintype "passive"))
      (node (ref "BLE_FRIEND") (pin "7") (pinfunction "7_7") (pintype "passive"))
      (node (ref "C1") (pin "2") (pinfunction "2_2") (pintype "passive"))
      (node (ref "C10") (pin "1") (pinfunction "1_1") (pintype "passive"))
      (node (ref "C11") (pin "2") (pinfunction "2_2") (pintype "passive"))
      (node (ref "C12") (pin "2") (pinfunction "2_2") (pintype "passive"))
      (node (ref "C13") (pin "2") (pinfunction "2_2") (pintype "passive"))
      (node (ref "C14") (pin "2") (pinfunction "2_2") (pintype "passive"))
      (node (ref "C15") (pin "2") (pinfunction "2_2") (pintype "passive"))
      (node (ref "C2") (pin "2") (pinfunction "2_2") (pintype "passive"))
      (node (ref "C3") (pin "2") (pinfunction "2_2") (pintype "passive"))
      (node (ref "C4") (pin "2") (pinfunction "2_2") (pintype "passive"))
      (node (ref "C5") (pin "2") (pinfunction "2_2") (pintype "passive"))
      (node (ref "C6") (pin "2") (pinfunction "2_2") (pintype "passive"))
      (node (ref "C7") (pin "2") (pinfunction "2_2") (pintype "passive"))
      (node (ref "C8") (pin "2") (pinfunction "2_2") (pintype "passive"))
      (node (ref "C9") (pin "2") (pinfunction "2_2") (pintype "passive"))
      (node (ref "HC05") (pin "4") (pinfunction "4_4") (pintype "passive"))
      (node (ref "IC1") (pin "1") (pinfunction "GND/ADJ_1") (pintype "input"))
      (node (ref "IC2") (pin "1") (pinfunction "ADJ_1") (pintype "input"))
      (node (ref "IC3") (pin "11") (pinfunction "GND_11") (pintype "power_in"))
      (node (ref "IC3") (pin "32") (pinfunction "GND1_32") (pintype "power_in"))
      (node (ref "IC3") (pin "62") (pinfunction "GND2_62") (pintype "power_in"))
      (node (ref "IC3") (pin "81") (pinfunction "GND3_81") (pintype "power_in"))
      (node (ref "IC3") (pin "99") (pinfunction "AGND_99") (pintype "power_in"))
      (node (ref "IC4") (pin "2") (pinfunction "GND_2") (pintype "power_in"))
      (node (ref "IC5") (pin "2") (pinfunction "GND_2") (pintype "passive"))
      (node (ref "IC6") (pin "2") (pinfunction "GND_2") (pintype "passive"))
      (node (ref "J1") (pin "GND") (pinfunction "GND_GND") (pintype "bidirectional"))
      (node (ref "J1") (pin "GNDBREAK") (pinfunction "GNDBREAK_GNDBREAK") (pintype "bidirectional"))
      (node (ref "JP1") (pin "2") (pinfunction "2_2") (pintype "passive"))
      (node (ref "LED1") (pin "2") (pinfunction "2_2") (pintype "passive"))
      (node (ref "LED2") (pin "2") (pinfunction "2_2") (pintype "passive"))
      (node (ref "LED3") (pin "2") (pinfunction "2_2") (pintype "passive"))
      (node (ref "MPU") (pin "2") (pinfunction "2_2") (pintype "passive"))
      (node (ref "MPU") (pin "7") (pinfunction "7_7") (pintype "passive"))
      (node (ref "ON") (pin "K") (pinfunction "C_K") (pintype "passive"))
      (node (ref "PROGRAM") (pin "6") (pinfunction "6_6") (pintype "passive"))
      (node (ref "R13") (pin "1") (pinfunction "1_1") (pintype "passive"))
      (node (ref "R14") (pin "1") (pinfunction "1_1") (pintype "passive"))
      (node (ref "R15") (pin "1") (pinfunction "1_1") (pintype "passive"))
      (node (ref "RESET") (pin "1") (pinfunction "1_1") (pintype "passive"))
      (node (ref "RESET") (pin "2") (pinfunction "2_2") (pintype "passive"))
      (node (ref "SERV01") (pin "3") (pinfunction "3_3") (pintype "passive"))
      (node (ref "SERV02") (pin "3") (pinfunction "3_3") (pintype "passive"))
      (node (ref "SERV03") (pin "3") (pinfunction "3_3") (pintype "passive"))
      (node (ref "TMP102") (pin "1") (pinfunction "1_1") (pintype "passive"))
      (node (ref "TMP102") (pin "6") (pinfunction "6_6") (pintype "passive"))
      (node (ref "Y1") (pin "2") (pinfunction "2_2") (pintype "passive"))
    )
    (net (code "110") (name "Net-(ON-PadA)") (class "Default")
      (node (ref "ON") (pin "A") (pinfunction "A_A") (pintype "passive"))
      (node (ref "R1") (pin "2") (pinfunction "2_2") (pintype "passive"))
    )
    (net (code "111") (name "VCC") (class "Default")
      (node (ref "C1") (pin "1") (pinfunction "1_1") (pintype "passive"))
      (node (ref "C13") (pin "1") (pinfunction "1_1") (pintype "passive"))
      (node (ref "C14") (pin "1") (pinfunction "1_1") (pintype "passive"))
      (node (ref "C2") (pin "1") (pinfunction "1_1") (pintype "passive"))
      (node (ref "D1") (pin "C") (pinfunction "C_C") (pintype "passive"))
      (node (ref "IC1") (pin "3") (pinfunction "IN_3") (pintype "input"))
      (node (ref "IC2") (pin "3") (pinfunction "VI_3") (pintype "input"))
      (node (ref "IC5") (pin "1") (pinfunction "VI_1") (pintype "input"))
      (node (ref "IC6") (pin "1") (pinfunction "VI_1") (pintype "input"))
    )
    (net (code "112") (name "unconnected-(IC4-NC{slash}FB-Pad4)") (class "Default")
      (node (ref "IC4") (pin "4") (pinfunction "NC/FB_4") (pintype "passive"))
    )
  )
)
